# SUP_1_5_3_3.net
KiCad netlist of a schematic drawn in Altium Designer
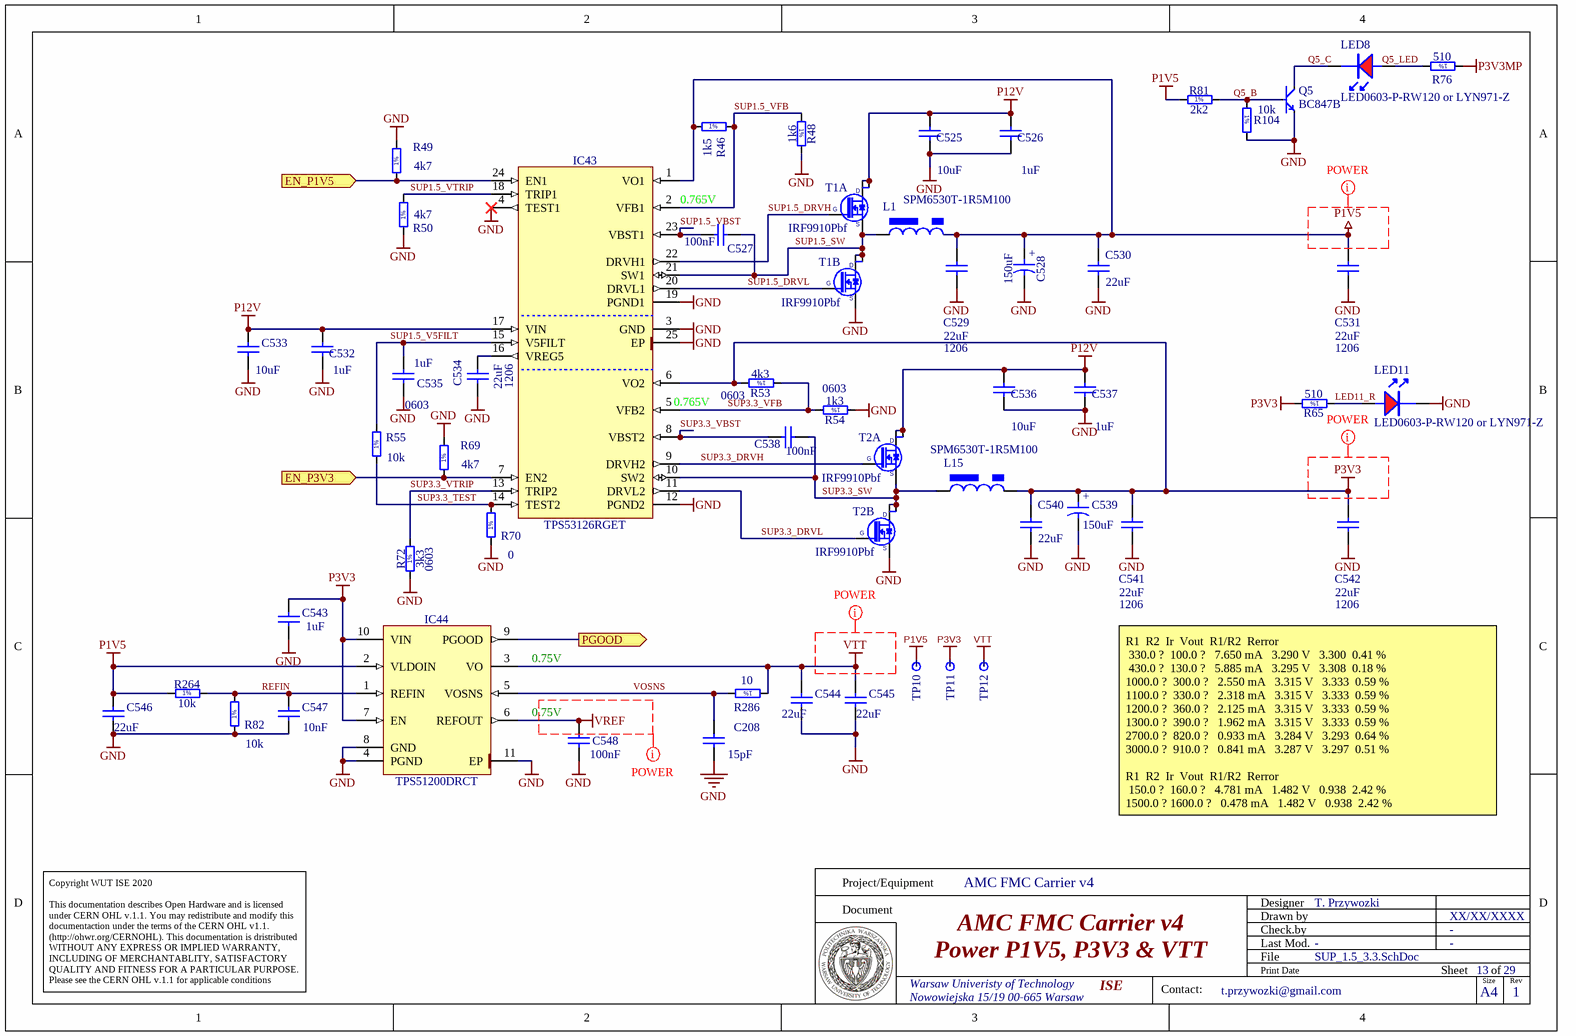
[diagram p0: SUP_1.5_3.3.SchDoc]

(export (version "E")
  (design (tool "Eeschema 10.0.6"))
  (components
    (comp (ref "C208")
      (value "15pF")
      (footprint "CAPC1005X55N")
      (description "Non-polarised capacitor")
      (fields
        (field (name "PART NUMBER") "CC0402_15PF_50V_5%_NP0")
        (field (name "VOLTAGE") "50V")
        (field (name "AUTHOR") "CERN DEM JLC")
      )
      (libsource (lib "Capacitors") (part "Capacitor - non polarized"))
    )
    (comp (ref "C525")
      (value "10uF")
      (footprint "CAPC2012X135N")
      (description "Non-polarised capacitor")
      (fields
        (field (name "PART NUMBER") "CC0805_10UF_16V_10%_X5R")
        (field (name "VOLTAGE") "16V")
        (field (name "AUTHOR") "CERN DEM JLC")
      )
      (libsource (lib "Capacitors") (part "Capacitor - non polarized"))
    )
    (comp (ref "C526")
      (value "1uF")
      (footprint "CAPC1608X87N")
      (description "Non-polarised capacitor")
      (fields
        (field (name "PART NUMBER") "CC0603_1UF_16V_10%_X7R")
        (field (name "VOLTAGE") "16V")
        (field (name "AUTHOR") "CERN DEM JLC")
      )
      (libsource (lib "Capacitors") (part "Capacitor - non polarized"))
    )
    (comp (ref "C527")
      (value "100nF")
      (footprint "CAPC1005X55N")
      (description "Non-polarised capacitor")
      (fields
        (field (name "PART NUMBER") "CC0402_100NF_16V_10%_X7R")
        (field (name "VOLTAGE") "16V")
        (field (name "AUTHOR") "CERN DEM JLC")
      )
      (libsource (lib "Capacitors") (part "Capacitor - non polarized"))
    )
    (comp (ref "C528")
      (value "150uF")
      (footprint "CAPMP7343X200N")
      (description "Polarised capacitor")
      (fields
        (field (name "PART NUMBER") "CAEM7343-20_150UF_2V_20%_LESR0009")
        (field (name "VOLTAGE") "2V")
        (field (name "AUTHOR") "CERN DEM JLC")
      )
      (libsource (lib "Capacitors") (part "Capacitor - polarized"))
    )
    (comp (ref "C529")
      (value "22uF")
      (footprint "CAPC3216X180N")
      (description "Non-polarised capacitor")
      (fields
        (field (name "PART NUMBER") "CC1206_22UF_10V_10%_X7R")
        (field (name "VOLTAGE") "10V")
        (field (name "CASE") "1206")
        (field (name "AUTHOR") "CERN DEM JLC")
      )
      (libsource (lib "Capacitors") (part "Capacitor - non polarized"))
    )
    (comp (ref "C530")
      (value "22uF")
      (footprint "CAPC3216X180N")
      (description "Non-polarised capacitor")
      (fields
        (field (name "PART NUMBER") "CC1206_22UF_10V_10%_X7R")
        (field (name "VOLTAGE") "10V")
        (field (name "AUTHOR") "CERN DEM JLC")
      )
      (libsource (lib "Capacitors") (part "Capacitor - non polarized"))
    )
    (comp (ref "C531")
      (value "22uF")
      (footprint "CAPC3216X180N")
      (description "Non-polarised capacitor")
      (fields
        (field (name "PART NUMBER") "CC1206_22UF_10V_10%_X7R")
        (field (name "VOLTAGE") "10V")
        (field (name "CASE") "1206")
        (field (name "AUTHOR") "CERN DEM JLC")
      )
      (libsource (lib "Capacitors") (part "Capacitor - non polarized"))
    )
    (comp (ref "C532")
      (value "1uF")
      (footprint "CAPC1608X87N")
      (description "Non-polarised capacitor")
      (fields
        (field (name "PART NUMBER") "CC0603_1UF_16V_10%_X7R")
        (field (name "VOLTAGE") "16V")
        (field (name "AUTHOR") "CERN DEM JLC")
      )
      (libsource (lib "Capacitors") (part "Capacitor - non polarized"))
    )
    (comp (ref "C533")
      (value "10uF")
      (footprint "CAPC2012X135N")
      (description "Non-polarised capacitor")
      (fields
        (field (name "PART NUMBER") "CC0805_10UF_16V_10%_X5R")
        (field (name "VOLTAGE") "16V")
        (field (name "AUTHOR") "CERN DEM JLC")
      )
      (libsource (lib "Capacitors") (part "Capacitor - non polarized"))
    )
    (comp (ref "C534")
      (value "22uF")
      (footprint "CAPC3216X180N")
      (description "Non-polarised capacitor")
      (fields
        (field (name "PART NUMBER") "CC1206_22UF_10V_10%_X7R")
        (field (name "VOLTAGE") "10V")
        (field (name "CASE") "1206")
        (field (name "AUTHOR") "CERN DEM JLC")
      )
      (libsource (lib "Capacitors") (part "Capacitor - non polarized"))
    )
    (comp (ref "C535")
      (value "1uF")
      (footprint "CAPC1608X87N")
      (description "Non-polarised capacitor")
      (fields
        (field (name "PART NUMBER") "CC0603_1UF_16V_10%_X7R")
        (field (name "VOLTAGE") "16V")
        (field (name "CASE") "0603")
        (field (name "AUTHOR") "CERN DEM JLC")
      )
      (libsource (lib "Capacitors") (part "Capacitor - non polarized"))
    )
    (comp (ref "C536")
      (value "10uF")
      (footprint "CAPC2012X135N")
      (description "Non-polarised capacitor")
      (fields
        (field (name "PART NUMBER") "CC0805_10UF_16V_10%_X5R")
        (field (name "VOLTAGE") "16V")
        (field (name "AUTHOR") "CERN DEM JLC")
      )
      (libsource (lib "Capacitors") (part "Capacitor - non polarized"))
    )
    (comp (ref "C537")
      (value "1uF")
      (footprint "CAPC1608X87N")
      (description "Non-polarised capacitor")
      (fields
        (field (name "PART NUMBER") "CC0603_1UF_16V_10%_X7R")
        (field (name "VOLTAGE") "16V")
        (field (name "AUTHOR") "CERN DEM JLC")
      )
      (libsource (lib "Capacitors") (part "Capacitor - non polarized"))
    )
    (comp (ref "C538")
      (value "100nF")
      (footprint "CAPC1005X55N")
      (description "Non-polarised capacitor")
      (fields
        (field (name "PART NUMBER") "CC0402_100NF_16V_10%_X7R")
        (field (name "VOLTAGE") "16V")
        (field (name "AUTHOR") "CERN DEM JLC")
      )
      (libsource (lib "Capacitors") (part "Capacitor - non polarized"))
    )
    (comp (ref "C539")
      (value "150uF")
      (footprint "CAPMP7343X200N")
      (description "Polarised capacitor")
      (fields
        (field (name "PART NUMBER") "CAEM7343-20_150UF_4V_20%_LESR0016")
        (field (name "VOLTAGE") "4V")
        (field (name "AUTHOR") "CERN DEM JLC")
      )
      (libsource (lib "Capacitors") (part "Capacitor - polarized"))
    )
    (comp (ref "C540")
      (value "22uF")
      (footprint "CAPC3216X180N")
      (description "Non-polarised capacitor")
      (fields
        (field (name "PART NUMBER") "CC1206_22UF_10V_10%_X7R")
        (field (name "VOLTAGE") "10V")
        (field (name "AUTHOR") "CERN DEM JLC")
      )
      (libsource (lib "Capacitors") (part "Capacitor - non polarized"))
    )
    (comp (ref "C541")
      (value "22uF")
      (footprint "CAPC3216X180N")
      (description "Non-polarised capacitor")
      (fields
        (field (name "PART NUMBER") "CC1206_22UF_10V_10%_X7R")
        (field (name "VOLTAGE") "10V")
        (field (name "CASE") "1206")
        (field (name "AUTHOR") "CERN DEM JLC")
      )
      (libsource (lib "Capacitors") (part "Capacitor - non polarized"))
    )
    (comp (ref "C542")
      (value "22uF")
      (footprint "CAPC3216X180N")
      (description "Non-polarised capacitor")
      (fields
        (field (name "PART NUMBER") "CC1206_22UF_10V_10%_X7R")
        (field (name "VOLTAGE") "10V")
        (field (name "CASE") "1206")
        (field (name "AUTHOR") "CERN DEM JLC")
      )
      (libsource (lib "Capacitors") (part "Capacitor - non polarized"))
    )
    (comp (ref "C543")
      (value "1uF")
      (footprint "CAPC1608X87N")
      (description "Non-polarised capacitor")
      (fields
        (field (name "PART NUMBER") "CC0603_1UF_16V_10%_X7R")
        (field (name "VOLTAGE") "16V")
        (field (name "AUTHOR") "CERN DEM JLC")
      )
      (libsource (lib "Capacitors") (part "Capacitor - non polarized"))
    )
    (comp (ref "C544")
      (value "22uF")
      (footprint "CAPC3216X180N")
      (description "Non-polarised capacitor")
      (fields
        (field (name "PART NUMBER") "CC1206_22UF_10V_10%_X7R")
        (field (name "VOLTAGE") "10V")
        (field (name "AUTHOR") "CERN DEM JLC")
      )
      (libsource (lib "Capacitors") (part "Capacitor - non polarized"))
    )
    (comp (ref "C545")
      (value "22uF")
      (footprint "CAPC3216X180N")
      (description "Non-polarised capacitor")
      (fields
        (field (name "PART NUMBER") "CC1206_22UF_10V_10%_X7R")
        (field (name "VOLTAGE") "10V")
        (field (name "AUTHOR") "CERN DEM JLC")
      )
      (libsource (lib "Capacitors") (part "Capacitor - non polarized"))
    )
    (comp (ref "C546")
      (value "22uF")
      (footprint "CAPC3216X180N")
      (description "Non-polarised capacitor")
      (fields
        (field (name "PART NUMBER") "CC1206_22UF_10V_10%_X7R")
        (field (name "VOLTAGE") "10V")
        (field (name "AUTHOR") "CERN DEM JLC")
      )
      (libsource (lib "Capacitors") (part "Capacitor - non polarized"))
    )
    (comp (ref "C547")
      (value "10nF")
      (footprint "CAPC1005X55N")
      (description "Non-polarised capacitor")
      (fields
        (field (name "PART NUMBER") "CC0402_10NF_16V_10%_X7R")
        (field (name "VOLTAGE") "16V")
        (field (name "AUTHOR") "CERN DEM JLC")
      )
      (libsource (lib "Capacitors") (part "Capacitor - non polarized"))
    )
    (comp (ref "C548")
      (value "100nF")
      (footprint "CAPC0603X33N")
      (description "Non-polarised capacitor")
      (fields
        (field (name "PART NUMBER") "CC0201_100NF_6.3V_10%_X5R")
        (field (name "VOLTAGE") "6.3V")
        (field (name "AUTHOR") "CERN DEM JLC")
      )
      (libsource (lib "Capacitors") (part "Capacitor - non polarized"))
    )
    (comp (ref "IC43")
      (value "TPS53126RGET")
      (footprint "QFN50P400X400X100-25N-S255")
      (description "Dual Synchronous Step-Down Controller For Low Voltage Power Rails")
      (fields (field (name "MANUFACTURER") "TEXAS INSTRUMENTS") (field (name "AUTHOR") "CERN DEM JLC"))
      (libsource (lib "ICs And Semiconductors") (part "TPS53126RGET"))
    )
    (comp (ref "IC44")
      (value "TPS51200DRCT")
      (footprint "SON50P300X300X100-11N-R175X250")
      (description "Sink/Source DDR Termination Regulator")
      (fields (field (name "MANUFACTURER") "TEXAS INSTRUMENTS") (field (name "AUTHOR") "CERN DEM JLC"))
      (libsource (lib "ICs And Semiconductors") (part "TPS51200DRC"))
    )
    (comp (ref "L1")
      (value "SPM6530T-1R5M100")
      (footprint "IND_TDK_SPM6530")
      (description "1.5uH, 20%, 10mR, 11.5A")
      (libsource (lib "LIBRARY_SCH") (part "L_POWER_SPM6530T"))
    )
    (comp (ref "L15")
      (value "SPM6530T-1R5M100")
      (footprint "IND_TDK_SPM6530")
      (description "1.5uH, 20%, 10mR, 11.5A")
      (libsource (lib "LIBRARY_SCH") (part "L_POWER_SPM6530T"))
    )
    (comp (ref "LED8")
      (value "LED0603-P-RW120 or LYN971-Z")
      (footprint "led_0603R")
      (description "LED 0603 red")
      (libsource (lib "LIBRARY_SCH") (part "LED_0603R"))
    )
    (comp (ref "LED11")
      (value "LED0603-P-RW120 or LYN971-Z")
      (footprint "led_0603R")
      (description "LED 0603 red")
      (libsource (lib "LIBRARY_SCH") (part "LED_0603R"))
    )
    (comp (ref "Q5")
      (value "BC847B")
      (footprint "SOT-23")
      (description "Transistor")
      (libsource (lib "LIBRARY_SCH") (part "Q_BC847B"))
    )
    (comp (ref "R46")
      (value "1k5")
      (footprint "RESC1608X55N")
      (description "Resistor - 1%")
      (fields
        (field (name "PART NUMBER") "R0603_1K5_1%_0.1W_100PPM")
        (field (name "POWER") "0.1W")
        (field (name "AUTHOR") "CERN DEM JLC")
      )
      (libsource (lib "Resistors") (part "Resistor - 1%"))
    )
    (comp (ref "R48")
      (value "1k6")
      (footprint "RESC1608X55N")
      (description "Resistor - 1%")
      (fields
        (field (name "PART NUMBER") "R0603_1K6_1%_0.1W_100PPM")
        (field (name "POWER") "0.1W")
        (field (name "AUTHOR") "CERN DEM JLC")
      )
      (libsource (lib "Resistors") (part "Resistor - 1%"))
    )
    (comp (ref "R49")
      (value "4k7")
      (footprint "RESC1005X40N")
      (description "Resistor - 1%")
      (fields
        (field (name "PART NUMBER") "R0402_4K7_1%_0.0625W_100PPM")
        (field (name "POWER") "0.0625W")
        (field (name "AUTHOR") "CERN DEM JLC")
      )
      (libsource (lib "Resistors") (part "Resistor - 1%"))
    )
    (comp (ref "R50")
      (value "4k7")
      (footprint "RESC1005X40N")
      (description "Resistor - 1%")
      (fields
        (field (name "PART NUMBER") "R0402_4K7_1%_0.0625W_100PPM")
        (field (name "POWER") "0.0625W")
        (field (name "AUTHOR") "CERN DEM JLC")
      )
      (libsource (lib "Resistors") (part "Resistor - 1%"))
    )
    (comp (ref "R53")
      (value "4k3")
      (footprint "RESC1608X55N")
      (description "Resistor - 1%")
      (fields
        (field (name "PART NUMBER") "R0603_4K3_1%_0.1W_100PPM")
        (field (name "POWER") "0.1W")
        (field (name "CASE") "0603")
        (field (name "AUTHOR") "CERN DEM JLC")
      )
      (libsource (lib "Resistors") (part "Resistor - 1%"))
    )
    (comp (ref "R54")
      (value "1k3")
      (footprint "RESC1608X55N")
      (description "Resistor - 1%")
      (fields
        (field (name "PART NUMBER") "R0603_1K3_1%_0.1W_100PPM")
        (field (name "POWER") "0.1W")
        (field (name "CASE") "0603")
        (field (name "AUTHOR") "CERN DEM JLC")
      )
      (libsource (lib "Resistors") (part "Resistor - 1%"))
    )
    (comp (ref "R55")
      (value "10k")
      (footprint "RESC1005X40N")
      (description "Resistor - 1%")
      (fields
        (field (name "PART NUMBER") "R0402_10K_1%_0.0625W_100PPM")
        (field (name "POWER") "0.0625W")
        (field (name "AUTHOR") "CERN DEM JLC")
      )
      (libsource (lib "Resistors") (part "Resistor - 1%"))
    )
    (comp (ref "R65")
      (value "510")
      (footprint "RESC1005X40N")
      (description "Resistor - 1%")
      (fields
        (field (name "PART NUMBER") "R0402_510R_1%_0.0625W_100PPM")
        (field (name "POWER") "0.0625W")
        (field (name "AUTHOR") "CERN DEM JLC")
      )
      (libsource (lib "Resistors") (part "Resistor - 1%"))
    )
    (comp (ref "R69")
      (value "4k7")
      (footprint "RESC1005X40N")
      (description "Resistor - 1%")
      (fields
        (field (name "PART NUMBER") "R0402_4K7_1%_0.0625W_100PPM")
        (field (name "POWER") "0.0625W")
        (field (name "AUTHOR") "CERN DEM JLC")
      )
      (libsource (lib "Resistors") (part "Resistor - 1%"))
    )
    (comp (ref "R70")
      (value "0")
      (footprint "RESC1005X40N")
      (description "Resistor - 1%")
      (fields
        (field (name "PART NUMBER") "R0402_0R_JUMPER")
        (field (name "MANUFACTURER") "GENERIC")
        (field (name "AUTHOR") "CERN DEM JLC")
      )
      (libsource (lib "Resistors") (part "Resistor - 1%"))
    )
    (comp (ref "R72")
      (value "3k3")
      (footprint "RESC1608X55N")
      (description "Resistor - 1%")
      (fields
        (field (name "PART NUMBER") "R0603_3K3_1%_0.1W_100PPM")
        (field (name "POWER") "0.1W")
        (field (name "CASE") "0603")
        (field (name "AUTHOR") "CERN DEM JLC")
      )
      (libsource (lib "Resistors") (part "Resistor - 1%"))
    )
    (comp (ref "R76")
      (value "510")
      (footprint "RESC1005X40N")
      (description "Resistor - 1%")
      (fields
        (field (name "PART NUMBER") "R0402_510R_1%_0.0625W_100PPM")
        (field (name "POWER") "0.0625W")
        (field (name "AUTHOR") "CERN DEM JLC")
      )
      (libsource (lib "Resistors") (part "Resistor - 1%"))
    )
    (comp (ref "R81")
      (value "2k2")
      (footprint "RESC1005X40N")
      (description "Resistor - 1%")
      (fields
        (field (name "PART NUMBER") "R0402_2K2_1%_0.0625W_100PPM")
        (field (name "POWER") "0.0625W")
        (field (name "AUTHOR") "CERN DEM JLC")
      )
      (libsource (lib "Resistors") (part "Resistor - 1%"))
    )
    (comp (ref "R82")
      (value "10k")
      (footprint "RESC1005X40N")
      (description "Resistor - 1%")
      (fields
        (field (name "PART NUMBER") "R0402_10K_1%_0.0625W_100PPM")
        (field (name "POWER") "0.0625W")
        (field (name "AUTHOR") "CERN DEM JLC")
      )
      (libsource (lib "Resistors") (part "Resistor - 1%"))
    )
    (comp (ref "R104")
      (value "10k")
      (footprint "RESC1005X40N")
      (description "Resistor - 1%")
      (fields
        (field (name "PART NUMBER") "R0402_10K_1%_0.0625W_100PPM")
        (field (name "POWER") "0.0625W")
        (field (name "AUTHOR") "CERN DEM JLC")
      )
      (libsource (lib "Resistors") (part "Resistor - 1%"))
    )
    (comp (ref "R264")
      (value "10k")
      (footprint "RESC1005X40N")
      (description "Resistor - 1%")
      (fields
        (field (name "PART NUMBER") "R0402_10K_1%_0.0625W_100PPM")
        (field (name "POWER") "0.0625W")
        (field (name "AUTHOR") "CERN DEM JLC")
      )
      (libsource (lib "Resistors") (part "Resistor - 1%"))
    )
    (comp (ref "R286")
      (value "10")
      (footprint "RESC1005X40N")
      (description "Resistor - 1%")
      (fields
        (field (name "PART NUMBER") "R0402_10R_1%_0.0625W_200PPM")
        (field (name "POWER") "0.0625W")
        (field (name "AUTHOR") "CERN DEM JLC")
      )
      (libsource (lib "Resistors") (part "Resistor - 1%"))
    )
    (comp (ref "T1")
      (value "IRF9910Pbf")
      (footprint "SOIC127P600X175-8N")
      (description "Dual SO-8 MOSFET For POL Cconverter")
      (fields (field (name "MANUFACTURER") "INTERNATIONAL RECTIFIER") (field (name "AUTHOR") "CERN DEM JLC"))
      (libsource (lib "ICs And Semiconductors") (part "IRF9910"))
    )
    (comp (ref "T2")
      (value "IRF9910Pbf")
      (footprint "SOIC127P600X175-8N")
      (description "Dual SO-8 MOSFET For POL Cconverter")
      (fields (field (name "MANUFACTURER") "INTERNATIONAL RECTIFIER") (field (name "AUTHOR") "CERN DEM JLC"))
      (libsource (lib "ICs And Semiconductors") (part "IRF9910"))
    )
    (comp (ref "TP10")
      (value "Test Point")
      (footprint "TPS127")
      (fields (field (name "PART NUMBER") "SMD_PAD_1.27X1.27MM") (field (name "AUTHOR") "CERN DEM JLC"))
      (libsource (lib "Eletro-mechanical") (part "Test Point"))
    )
    (comp (ref "TP11")
      (value "Test Point")
      (footprint "TPS127")
      (fields (field (name "PART NUMBER") "SMD_PAD_1.27X1.27MM") (field (name "AUTHOR") "CERN DEM JLC"))
      (libsource (lib "Eletro-mechanical") (part "Test Point"))
    )
    (comp (ref "TP12")
      (value "Test Point")
      (footprint "TPS127")
      (fields (field (name "PART NUMBER") "SMD_PAD_1.27X1.27MM") (field (name "AUTHOR") "CERN DEM JLC"))
      (libsource (lib "Eletro-mechanical") (part "Test Point"))
    )
  )
  (nets
    (net (code "1") (name "/EN_P1V5") (class "Default")
      (node (ref "IC43") (pin "24") (pinfunction "EN1_24") (pintype "input"))
      (node (ref "R49") (pin "1") (pinfunction "1_1") (pintype "passive"))
    )
    (net (code "2") (name "/EN_P3V3") (class "Default")
      (node (ref "IC43") (pin "7") (pinfunction "EN2_7") (pintype "input"))
      (node (ref "R69") (pin "1") (pinfunction "1_1") (pintype "passive"))
    )
    (net (code "3") (name "/LED11_R") (class "Default")
      (node (ref "LED11") (pin "A") (pinfunction "A_A") (pintype "passive"))
      (node (ref "R65") (pin "1") (pinfunction "1_1") (pintype "passive"))
    )
    (net (code "4") (name "/PGOOD") (class "Default")
      (node (ref "IC44") (pin "9") (pinfunction "PGOOD_9") (pintype "output"))
    )
    (net (code "5") (name "/Q5_B") (class "Default")
      (node (ref "Q5") (pin "1") (pinfunction "B_1") (pintype "passive"))
      (node (ref "R104") (pin "1") (pinfunction "1_1") (pintype "passive"))
      (node (ref "R81") (pin "2") (pinfunction "2_2") (pintype "passive"))
    )
    (net (code "6") (name "/Q5_C") (class "Default")
      (node (ref "LED8") (pin "K") (pinfunction "K_K") (pintype "passive"))
      (node (ref "Q5") (pin "3") (pinfunction "C_3") (pintype "passive"))
    )
    (net (code "8") (name "/REFIN") (class "Default")
      (node (ref "C547") (pin "2") (pinfunction "2_2") (pintype "passive"))
      (node (ref "IC44") (pin "1") (pinfunction "REFIN_1") (pintype "input"))
      (node (ref "R264") (pin "2") (pinfunction "2_2") (pintype "passive"))
      (node (ref "R82") (pin "2") (pinfunction "2_2") (pintype "passive"))
    )
    (net (code "9") (name "/SUP1.5_DRVH") (class "Default")
      (node (ref "IC43") (pin "22") (pinfunction "DRVH1_22") (pintype "output"))
      (node (ref "T1") (pin "4") (pinfunction "G_4") (pintype "passive"))
    )
    (net (code "10") (name "/SUP1.5_DRVL") (class "Default")
      (node (ref "IC43") (pin "20") (pinfunction "DRVL1_20") (pintype "output"))
      (node (ref "T1") (pin "2") (pinfunction "G_2") (pintype "passive"))
    )
    (net (code "11") (name "/SUP1.5_SW") (class "Default")
      (node (ref "C527") (pin "1") (pinfunction "1_1") (pintype "passive"))
      (node (ref "IC43") (pin "21") (pinfunction "SW1_21") (pintype "bidirectional"))
      (node (ref "L1") (pin "1") (pintype "passive"))
      (node (ref "T1") (pin "3") (pinfunction "S_3") (pintype "passive"))
      (node (ref "T1") (pin "7") (pinfunction "D_7") (pintype "passive"))
      (node (ref "T1") (pin "8") (pinfunction "D_8") (pintype "passive"))
    )
    (net (code "12") (name "/SUP1.5_V5FILT") (class "Default")
      (node (ref "C535") (pin "2") (pinfunction "2_2") (pintype "passive"))
      (node (ref "IC43") (pin "15") (pinfunction "V5FILT_15") (pintype "input"))
      (node (ref "R55") (pin "2") (pinfunction "2_2") (pintype "passive"))
    )
    (net (code "13") (name "/SUP1.5_VBST") (class "Default")
      (node (ref "C527") (pin "2") (pinfunction "2_2") (pintype "passive"))
      (node (ref "IC43") (pin "23") (pinfunction "VBST1_23") (pintype "input"))
    )
    (net (code "14") (name "/SUP1.5_VFB") (class "Default")
      (node (ref "IC43") (pin "2") (pinfunction "VFB1_2") (pintype "input"))
      (node (ref "R46") (pin "2") (pinfunction "2_2") (pintype "passive"))
      (node (ref "R48") (pin "1") (pinfunction "1_1") (pintype "passive"))
    )
    (net (code "15") (name "/SUP1.5_VTRIP") (class "Default")
      (node (ref "IC43") (pin "18") (pinfunction "TRIP1_18") (pintype "input"))
      (node (ref "R50") (pin "2") (pinfunction "2_2") (pintype "passive"))
    )
    (net (code "16") (name "/SUP3.3_DRVH") (class "Default")
      (node (ref "IC43") (pin "9") (pinfunction "DRVH2_9") (pintype "output"))
      (node (ref "T2") (pin "4") (pinfunction "G_4") (pintype "passive"))
    )
    (net (code "17") (name "/SUP3.3_DRVL") (class "Default")
      (node (ref "IC43") (pin "11") (pinfunction "DRVL2_11") (pintype "output"))
      (node (ref "T2") (pin "2") (pinfunction "G_2") (pintype "passive"))
    )
    (net (code "18") (name "/SUP3.3_SW") (class "Default")
      (node (ref "C538") (pin "1") (pinfunction "1_1") (pintype "passive"))
      (node (ref "IC43") (pin "10") (pinfunction "SW2_10") (pintype "bidirectional"))
      (node (ref "L15") (pin "1") (pintype "passive"))
      (node (ref "T2") (pin "3") (pinfunction "S_3") (pintype "passive"))
      (node (ref "T2") (pin "7") (pinfunction "D_7") (pintype "passive"))
      (node (ref "T2") (pin "8") (pinfunction "D_8") (pintype "passive"))
    )
    (net (code "19") (name "/SUP3.3_TEST") (class "Default")
      (node (ref "IC43") (pin "14") (pinfunction "TEST2_14") (pintype "input"))
      (node (ref "R55") (pin "1") (pinfunction "1_1") (pintype "passive"))
      (node (ref "R70") (pin "2") (pinfunction "2_2") (pintype "passive"))
    )
    (net (code "20") (name "/SUP3.3_VBST") (class "Default")
      (node (ref "C538") (pin "2") (pinfunction "2_2") (pintype "passive"))
      (node (ref "IC43") (pin "8") (pinfunction "VBST2_8") (pintype "input"))
    )
    (net (code "21") (name "/SUP3.3_VFB") (class "Default")
      (node (ref "IC43") (pin "5") (pinfunction "VFB2_5") (pintype "input"))
      (node (ref "R53") (pin "1") (pinfunction "1_1") (pintype "passive"))
      (node (ref "R54") (pin "2") (pinfunction "2_2") (pintype "passive"))
    )
    (net (code "22") (name "/SUP3.3_VTRIP") (class "Default")
      (node (ref "IC43") (pin "13") (pinfunction "TRIP2_13") (pintype "input"))
      (node (ref "R72") (pin "2") (pinfunction "2_2") (pintype "passive"))
    )
    (net (code "23") (name "/VOSNS") (class "Default")
      (node (ref "C208") (pin "1") (pinfunction "1_1") (pintype "passive"))
      (node (ref "IC44") (pin "5") (pinfunction "VOSNS_5") (pintype "input"))
      (node (ref "R286") (pin "2") (pinfunction "2_2") (pintype "passive"))
    )
    (net (code "24") (name "GND") (class "Default")
      (node (ref "C208") (pin "2") (pinfunction "2_2") (pintype "passive"))
      (node (ref "C525") (pin "1") (pinfunction "1_1") (pintype "passive"))
      (node (ref "C526") (pin "1") (pinfunction "1_1") (pintype "passive"))
      (node (ref "C528") (pin "2") (pinfunction "2_2") (pintype "passive"))
      (node (ref "C529") (pin "2") (pinfunction "2_2") (pintype "passive"))
      (node (ref "C530") (pin "2") (pinfunction "2_2") (pintype "passive"))
      (node (ref "C531") (pin "2") (pinfunction "2_2") (pintype "passive"))
      (node (ref "C532") (pin "1") (pinfunction "1_1") (pintype "passive"))
      (node (ref "C533") (pin "1") (pinfunction "1_1") (pintype "passive"))
      (node (ref "C534") (pin "1") (pinfunction "1_1") (pintype "passive"))
      (node (ref "C535") (pin "1") (pinfunction "1_1") (pintype "passive"))
      (node (ref "C536") (pin "1") (pinfunction "1_1") (pintype "passive"))
      (node (ref "C537") (pin "1") (pinfunction "1_1") (pintype "passive"))
      (node (ref "C539") (pin "2") (pinfunction "2_2") (pintype "passive"))
      (node (ref "C540") (pin "2") (pinfunction "2_2") (pintype "passive"))
      (node (ref "C541") (pin "2") (pinfunction "2_2") (pintype "passive"))
      (node (ref "C542") (pin "2") (pinfunction "2_2") (pintype "passive"))
      (node (ref "C543") (pin "1") (pinfunction "1_1") (pintype "passive"))
      (node (ref "C544") (pin "1") (pinfunction "1_1") (pintype "passive"))
      (node (ref "C545") (pin "1") (pinfunction "1_1") (pintype "passive"))
      (node (ref "C546") (pin "1") (pinfunction "1_1") (pintype "passive"))
      (node (ref "C547") (pin "1") (pinfunction "1_1") (pintype "passive"))
      (node (ref "C548") (pin "1") (pinfunction "1_1") (pintype "passive"))
      (node (ref "IC43") (pin "12") (pinfunction "PGND2_12") (pintype "power_in"))
      (node (ref "IC43") (pin "19") (pinfunction "PGND1_19") (pintype "power_in"))
      (node (ref "IC43") (pin "25") (pinfunction "EP_25") (pintype "power_in"))
      (node (ref "IC43") (pin "3") (pinfunction "GND_3") (pintype "power_in"))
      (node (ref "IC43") (pin "4") (pinfunction "TEST1_4") (pintype "output"))
      (node (ref "IC44") (pin "11") (pinfunction "EP_11") (pintype "power_in"))
      (node (ref "IC44") (pin "4") (pinfunction "PGND_4") (pintype "power_in"))
      (node (ref "IC44") (pin "8") (pinfunction "GND_8") (pintype "power_in"))
      (node (ref "LED11") (pin "K") (pinfunction "K_K") (pintype "passive"))
      (node (ref "Q5") (pin "2") (pinfunction "E_2") (pintype "passive"))
      (node (ref "R104") (pin "2") (pinfunction "2_2") (pintype "passive"))
      (node (ref "R48") (pin "2") (pinfunction "2_2") (pintype "passive"))
      (node (ref "R49") (pin "2") (pinfunction "2_2") (pintype "passive"))
      (node (ref "R50") (pin "1") (pinfunction "1_1") (pintype "passive"))
      (node (ref "R54") (pin "1") (pinfunction "1_1") (pintype "passive"))
      (node (ref "R69") (pin "2") (pinfunction "2_2") (pintype "passive"))
      (node (ref "R70") (pin "1") (pinfunction "1_1") (pintype "passive"))
      (node (ref "R72") (pin "1") (pinfunction "1_1") (pintype "passive"))
      (node (ref "R82") (pin "1") (pinfunction "1_1") (pintype "passive"))
      (node (ref "T1") (pin "1") (pinfunction "S_1") (pintype "passive"))
      (node (ref "T2") (pin "1") (pinfunction "S_1") (pintype "passive"))
    )
    (net (code "25") (name "Net-(IC43-VREG5)") (class "Default")
      (node (ref "C534") (pin "2") (pinfunction "2_2") (pintype "passive"))
      (node (ref "IC43") (pin "16") (pinfunction "VREG5_16") (pintype "output"))
    )
    (net (code "26") (name "Net-(LED8-PadA)") (class "Default")
      (node (ref "LED8") (pin "A") (pinfunction "A_A") (pintype "passive"))
      (node (ref "R76") (pin "2") (pinfunction "2_2") (pintype "passive"))
    )
    (net (code "27") (name "P1V5") (class "Default")
      (node (ref "C528") (pin "1") (pinfunction "1_1") (pintype "passive"))
      (node (ref "C529") (pin "1") (pinfunction "1_1") (pintype "passive"))
      (node (ref "C530") (pin "1") (pinfunction "1_1") (pintype "passive"))
      (node (ref "C531") (pin "1") (pinfunction "1_1") (pintype "passive"))
      (node (ref "C546") (pin "2") (pinfunction "2_2") (pintype "passive"))
      (node (ref "IC43") (pin "1") (pinfunction "VO1_1") (pintype "input"))
      (node (ref "IC44") (pin "2") (pinfunction "VLDOIN_2") (pintype "input"))
      (node (ref "L1") (pin "2") (pintype "passive"))
      (node (ref "R264") (pin "1") (pinfunction "1_1") (pintype "passive"))
      (node (ref "R46") (pin "1") (pinfunction "1_1") (pintype "passive"))
      (node (ref "R81") (pin "1") (pinfunction "1_1") (pintype "passive"))
      (node (ref "TP10") (pin "1") (pinfunction "1_1") (pintype "bidirectional"))
    )
    (net (code "28") (name "P3V3") (class "Default")
      (node (ref "C539") (pin "1") (pinfunction "1_1") (pintype "passive"))
      (node (ref "C540") (pin "1") (pinfunction "1_1") (pintype "passive"))
      (node (ref "C541") (pin "1") (pinfunction "1_1") (pintype "passive"))
      (node (ref "C542") (pin "1") (pinfunction "1_1") (pintype "passive"))
      (node (ref "C543") (pin "2") (pinfunction "2_2") (pintype "passive"))
      (node (ref "IC43") (pin "6") (pinfunction "VO2_6") (pintype "input"))
      (node (ref "IC44") (pin "10") (pinfunction "VIN_10") (pintype "power_in"))
      (node (ref "IC44") (pin "7") (pinfunction "EN_7") (pintype "input"))
      (node (ref "L15") (pin "2") (pintype "passive"))
      (node (ref "R53") (pin "2") (pinfunction "2_2") (pintype "passive"))
      (node (ref "R65") (pin "2") (pinfunction "2_2") (pintype "passive"))
      (node (ref "TP11") (pin "1") (pinfunction "1_1") (pintype "bidirectional"))
    )
    (net (code "29") (name "P3V3MP") (class "Default")
      (node (ref "R76") (pin "1") (pinfunction "1_1") (pintype "passive"))
    )
    (net (code "30") (name "P12V") (class "Default")
      (node (ref "C525") (pin "2") (pinfunction "2_2") (pintype "passive"))
      (node (ref "C526") (pin "2") (pinfunction "2_2") (pintype "passive"))
      (node (ref "C532") (pin "2") (pinfunction "2_2") (pintype "passive"))
      (node (ref "C533") (pin "2") (pinfunction "2_2") (pintype "passive"))
      (node (ref "C536") (pin "2") (pinfunction "2_2") (pintype "passive"))
      (node (ref "C537") (pin "2") (pinfunction "2_2") (pintype "passive"))
      (node (ref "IC43") (pin "17") (pinfunction "VIN_17") (pintype "input"))
      (node (ref "T1") (pin "5") (pinfunction "D_5") (pintype "passive"))
      (node (ref "T1") (pin "6") (pinfunction "D_6") (pintype "passive"))
      (node (ref "T2") (pin "5") (pinfunction "D_5") (pintype "passive"))
      (node (ref "T2") (pin "6") (pinfunction "D_6") (pintype "passive"))
    )
    (net (code "31") (name "VREF") (class "Default")
      (node (ref "C548") (pin "2") (pinfunction "2_2") (pintype "passive"))
      (node (ref "IC44") (pin "6") (pinfunction "REFOUT_6") (pintype "output"))
    )
    (net (code "32") (name "VTT") (class "Default")
      (node (ref "C544") (pin "2") (pinfunction "2_2") (pintype "passive"))
      (node (ref "C545") (pin "2") (pinfunction "2_2") (pintype "passive"))
      (node (ref "IC44") (pin "3") (pinfunction "VO_3") (pintype "power_in"))
      (node (ref "R286") (pin "1") (pinfunction "1_1") (pintype "passive"))
      (node (ref "TP12") (pin "1") (pinfunction "1_1") (pintype "bidirectional"))
    )
  )
)
